# base_1.net
KiCad netlist of a schematic drawn in EAGLE
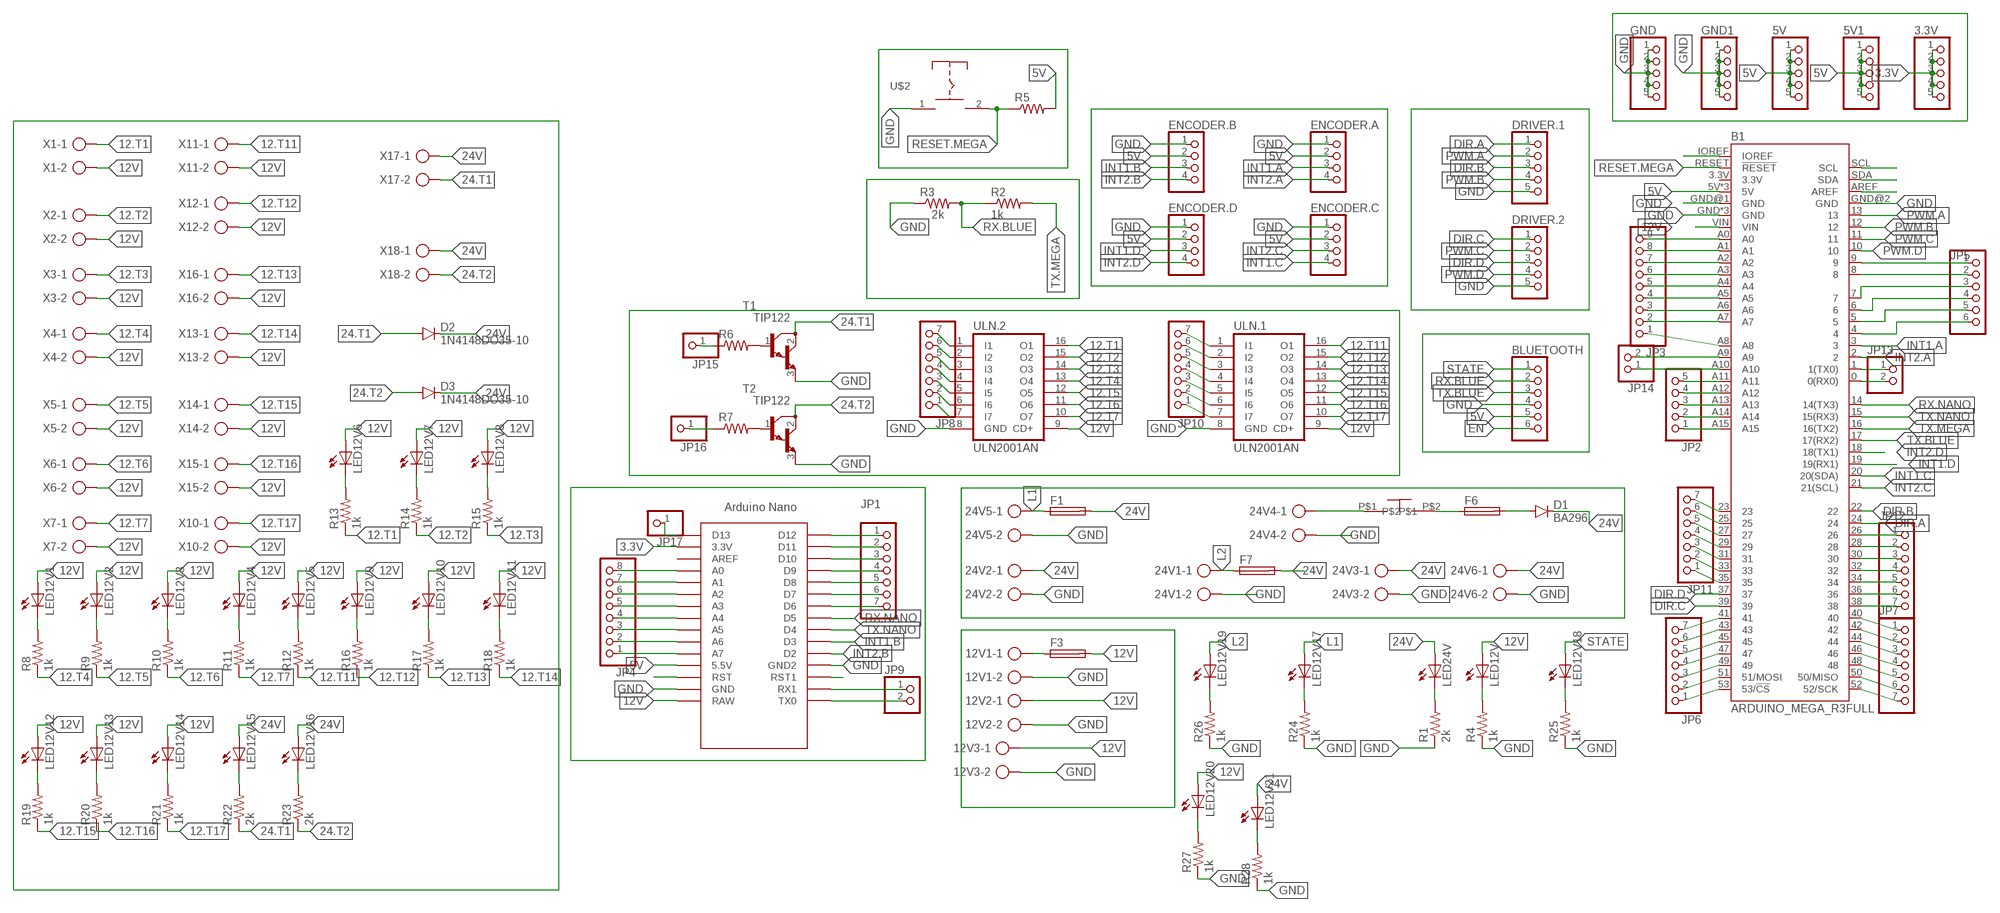
[diagram p0: schematic, sheet 1]

(export (version "E")
  (design (tool "Eeschema 10.0.6"))
  (components
    (comp (ref "3.3V")
      (value "PINHD-1X5")
      (footprint "eagle-import:1X05")
      (libsource (lib "eagle-import") (part "PINHD-1X5"))
    )
    (comp (ref "5V")
      (value "PINHD-1X5")
      (footprint "eagle-import:1X05")
      (libsource (lib "eagle-import") (part "PINHD-1X5"))
    )
    (comp (ref "5V1")
      (value "PINHD-1X5")
      (footprint "eagle-import:1X05")
      (libsource (lib "eagle-import") (part "PINHD-1X5"))
    )
    (comp (ref "12V1")
      (value "AK300/2")
      (footprint "eagle-import:AK300_2")
      (libsource (lib "eagle-import") (part "AK300/2"))
    )
    (comp (ref "12V2")
      (value "AK300/2")
      (footprint "eagle-import:AK300_2")
      (libsource (lib "eagle-import") (part "AK300/2"))
    )
    (comp (ref "12V3")
      (value "AK300/2")
      (footprint "eagle-import:AK300_2")
      (libsource (lib "eagle-import") (part "AK300/2"))
    )
    (comp (ref "24V1")
      (value "W237-113")
      (footprint "eagle-import:W237-113")
      (libsource (lib "eagle-import") (part "W237-113"))
    )
    (comp (ref "24V2")
      (value "AK300/2")
      (footprint "eagle-import:AK300_2")
      (libsource (lib "eagle-import") (part "AK300/2"))
    )
    (comp (ref "24V3")
      (value "AK300/2")
      (footprint "eagle-import:AK300_2")
      (libsource (lib "eagle-import") (part "AK300/2"))
    )
    (comp (ref "24V4")
      (value "W237-113")
      (footprint "eagle-import:W237-113")
      (libsource (lib "eagle-import") (part "W237-113"))
    )
    (comp (ref "24V5")
      (value "W237-113")
      (footprint "eagle-import:W237-113")
      (libsource (lib "eagle-import") (part "W237-113"))
    )
    (comp (ref "24V6")
      (value "AK300/2")
      (footprint "eagle-import:AK300_2")
      (libsource (lib "eagle-import") (part "AK300/2"))
    )
    (comp (ref "B1")
      (value "ARDUINO_MEGA_R3FULL")
      (footprint "eagle-import:ARDUINO_MEGA_NO_SILK")
      (libsource (lib "eagle-import") (part "ARDUINO_MEGA_R3FULL"))
    )
    (comp (ref "BLUETOOTH")
      (value "PINHD-1X6")
      (footprint "eagle-import:1X06")
      (libsource (lib "eagle-import") (part "PINHD-1X6"))
    )
    (comp (ref "D1")
      (value "BA296")
      (footprint "eagle-import:P2-15")
      (libsource (lib "eagle-import") (part "BA296"))
    )
    (comp (ref "D2")
      (value "1N4148DO35-10")
      (footprint "eagle-import:DO35-10")
      (libsource (lib "eagle-import") (part "1N4148DO35-10"))
    )
    (comp (ref "D3")
      (value "1N4148DO35-10")
      (footprint "eagle-import:DO35-10")
      (libsource (lib "eagle-import") (part "1N4148DO35-10"))
    )
    (comp (ref "DRIVER.1")
      (value "PINHD-1X5")
      (footprint "eagle-import:1X05")
      (libsource (lib "eagle-import") (part "PINHD-1X5"))
    )
    (comp (ref "DRIVER.2")
      (value "PINHD-1X5")
      (footprint "eagle-import:1X05")
      (libsource (lib "eagle-import") (part "PINHD-1X5"))
    )
    (comp (ref "ENCODER.A")
      (value "PINHD-1X4")
      (footprint "eagle-import:1X04")
      (libsource (lib "eagle-import") (part "PINHD-1X4"))
    )
    (comp (ref "ENCODER.B")
      (value "PINHD-1X4")
      (footprint "eagle-import:1X04")
      (libsource (lib "eagle-import") (part "PINHD-1X4"))
    )
    (comp (ref "ENCODER.C")
      (value "PINHD-1X4")
      (footprint "eagle-import:1X04")
      (libsource (lib "eagle-import") (part "PINHD-1X4"))
    )
    (comp (ref "ENCODER.D")
      (value "PINHD-1X4")
      (footprint "eagle-import:1X04")
      (libsource (lib "eagle-import") (part "PINHD-1X4"))
    )
    (comp (ref "F1")
      (value "SH22,5A")
      (footprint "eagle-import:SH22,5A")
      (fields (field (name "MPN") "0031.7701.11"))
      (libsource (lib "eagle-import") (part "SH22,5A"))
    )
    (comp (ref "F3")
      (value "SH22,5A")
      (footprint "eagle-import:SH22,5A")
      (fields (field (name "MPN") "0031.7701.11"))
      (libsource (lib "eagle-import") (part "SH22,5A"))
    )
    (comp (ref "F6")
      (value "SH22,5A")
      (footprint "eagle-import:SH22,5A")
      (fields (field (name "MPN") "0031.7701.11"))
      (libsource (lib "eagle-import") (part "SH22,5A"))
    )
    (comp (ref "F7")
      (value "SH22,5A")
      (footprint "eagle-import:SH22,5A")
      (fields (field (name "MPN") "0031.7701.11"))
      (libsource (lib "eagle-import") (part "SH22,5A"))
    )
    (comp (ref "GND")
      (value "PINHD-1X5")
      (footprint "eagle-import:1X05")
      (libsource (lib "eagle-import") (part "PINHD-1X5"))
    )
    (comp (ref "GND1")
      (value "PINHD-1X5")
      (footprint "eagle-import:1X05")
      (libsource (lib "eagle-import") (part "PINHD-1X5"))
    )
    (comp (ref "JP1")
      (value "PINHD-1X7")
      (footprint "eagle-import:1X07")
      (libsource (lib "eagle-import") (part "PINHD-1X7"))
    )
    (comp (ref "JP2")
      (value "PINHD-1X5")
      (footprint "eagle-import:1X05")
      (libsource (lib "eagle-import") (part "PINHD-1X5"))
    )
    (comp (ref "JP3")
      (value "PINHD-1X9")
      (footprint "eagle-import:1X09")
      (libsource (lib "eagle-import") (part "PINHD-1X9"))
    )
    (comp (ref "JP4")
      (value "PINHD-1X8")
      (footprint "eagle-import:1X08")
      (libsource (lib "eagle-import") (part "PINHD-1X8"))
    )
    (comp (ref "JP5")
      (value "PINHD-1X6")
      (footprint "eagle-import:1X06")
      (libsource (lib "eagle-import") (part "PINHD-1X6"))
    )
    (comp (ref "JP6")
      (value "PINHD-1X7")
      (footprint "eagle-import:1X07")
      (libsource (lib "eagle-import") (part "PINHD-1X7"))
    )
    (comp (ref "JP7")
      (value "PINHD-1X7")
      (footprint "eagle-import:1X07")
      (libsource (lib "eagle-import") (part "PINHD-1X7"))
    )
    (comp (ref "JP8")
      (value "PINHD-1X7")
      (footprint "eagle-import:1X07")
      (libsource (lib "eagle-import") (part "PINHD-1X7"))
    )
    (comp (ref "JP9")
      (value "PINHD-1X2")
      (footprint "eagle-import:1X02")
      (libsource (lib "eagle-import") (part "PINHD-1X2"))
    )
    (comp (ref "JP10")
      (value "PINHD-1X7")
      (footprint "eagle-import:1X07")
      (libsource (lib "eagle-import") (part "PINHD-1X7"))
    )
    (comp (ref "JP11")
      (value "PINHD-1X7")
      (footprint "eagle-import:1X07")
      (libsource (lib "eagle-import") (part "PINHD-1X7"))
    )
    (comp (ref "JP12")
      (value "PINHD-1X7")
      (footprint "eagle-import:1X07")
      (libsource (lib "eagle-import") (part "PINHD-1X7"))
    )
    (comp (ref "JP13")
      (value "PINHD-1X2")
      (footprint "eagle-import:1X02")
      (libsource (lib "eagle-import") (part "PINHD-1X2"))
    )
    (comp (ref "JP14")
      (value "PINHD-1X2")
      (footprint "eagle-import:1X02")
      (libsource (lib "eagle-import") (part "PINHD-1X2"))
    )
    (comp (ref "JP15")
      (value "PINHD-1X1")
      (footprint "eagle-import:1X01")
      (libsource (lib "eagle-import") (part "PINHD-1X1"))
    )
    (comp (ref "JP16")
      (value "PINHD-1X1")
      (footprint "eagle-import:1X01")
      (libsource (lib "eagle-import") (part "PINHD-1X1"))
    )
    (comp (ref "JP17")
      (value "PINHD-1X1")
      (footprint "eagle-import:1X01")
      (libsource (lib "eagle-import") (part "PINHD-1X1"))
    )
    (comp (ref "LED12V")
      (value "LED5MM")
      (footprint "eagle-import:LED5MM")
      (libsource (lib "eagle-import") (part "LED5MM"))
    )
    (comp (ref "LED12V1")
      (value "LED3MM")
      (footprint "eagle-import:LED3MM")
      (libsource (lib "eagle-import") (part "LED3MM"))
    )
    (comp (ref "LED12V2")
      (value "LED3MM")
      (footprint "eagle-import:LED3MM")
      (libsource (lib "eagle-import") (part "LED3MM"))
    )
    (comp (ref "LED12V3")
      (value "LED3MM")
      (footprint "eagle-import:LED3MM")
      (libsource (lib "eagle-import") (part "LED3MM"))
    )
    (comp (ref "LED12V4")
      (value "LED3MM")
      (footprint "eagle-import:LED3MM")
      (libsource (lib "eagle-import") (part "LED3MM"))
    )
    (comp (ref "LED12V5")
      (value "LED3MM")
      (footprint "eagle-import:LED3MM")
      (libsource (lib "eagle-import") (part "LED3MM"))
    )
    (comp (ref "LED12V6")
      (value "LED3MM")
      (footprint "eagle-import:LED3MM")
      (libsource (lib "eagle-import") (part "LED3MM"))
    )
    (comp (ref "LED12V7")
      (value "LED3MM")
      (footprint "eagle-import:LED3MM")
      (libsource (lib "eagle-import") (part "LED3MM"))
    )
    (comp (ref "LED12V8")
      (value "LED3MM")
      (footprint "eagle-import:LED3MM")
      (libsource (lib "eagle-import") (part "LED3MM"))
    )
    (comp (ref "LED12V9")
      (value "LED3MM")
      (footprint "eagle-import:LED3MM")
      (libsource (lib "eagle-import") (part "LED3MM"))
    )
    (comp (ref "LED12V10")
      (value "LED3MM")
      (footprint "eagle-import:LED3MM")
      (libsource (lib "eagle-import") (part "LED3MM"))
    )
    (comp (ref "LED12V11")
      (value "LED3MM")
      (footprint "eagle-import:LED3MM")
      (libsource (lib "eagle-import") (part "LED3MM"))
    )
    (comp (ref "LED12V12")
      (value "LED3MM")
      (footprint "eagle-import:LED3MM")
      (libsource (lib "eagle-import") (part "LED3MM"))
    )
    (comp (ref "LED12V13")
      (value "LED3MM")
      (footprint "eagle-import:LED3MM")
      (libsource (lib "eagle-import") (part "LED3MM"))
    )
    (comp (ref "LED12V14")
      (value "LED3MM")
      (footprint "eagle-import:LED3MM")
      (libsource (lib "eagle-import") (part "LED3MM"))
    )
    (comp (ref "LED12V15")
      (value "LED3MM")
      (footprint "eagle-import:LED3MM")
      (libsource (lib "eagle-import") (part "LED3MM"))
    )
    (comp (ref "LED12V16")
      (value "LED3MM")
      (footprint "eagle-import:LED3MM")
      (libsource (lib "eagle-import") (part "LED3MM"))
    )
    (comp (ref "LED12V17")
      (value "LED3MM")
      (footprint "eagle-import:LED3MM")
      (libsource (lib "eagle-import") (part "LED3MM"))
    )
    (comp (ref "LED12V18")
      (value "LED3MM")
      (footprint "eagle-import:LED3MM")
      (libsource (lib "eagle-import") (part "LED3MM"))
    )
    (comp (ref "LED12V19")
      (value "LED3MM")
      (footprint "eagle-import:LED3MM")
      (libsource (lib "eagle-import") (part "LED3MM"))
    )
    (comp (ref "LED12V20")
      (value "LED3MM")
      (footprint "eagle-import:LED3MM")
      (libsource (lib "eagle-import") (part "LED3MM"))
    )
    (comp (ref "LED12V21")
      (value "LED3MM")
      (footprint "eagle-import:LED3MM")
      (libsource (lib "eagle-import") (part "LED3MM"))
    )
    (comp (ref "LED24V")
      (value "LED5MM")
      (footprint "eagle-import:LED5MM")
      (libsource (lib "eagle-import") (part "LED5MM"))
    )
    (comp (ref "R1")
      (value "2k")
      (footprint "eagle-import:0207_10")
      (libsource (lib "eagle-import") (part "R-US_0207/10"))
    )
    (comp (ref "R2")
      (value "1k")
      (footprint "eagle-import:0204_7")
      (libsource (lib "eagle-import") (part "R-US_0204/7"))
    )
    (comp (ref "R3")
      (value "2k")
      (footprint "eagle-import:0207_10")
      (libsource (lib "eagle-import") (part "R-US_0207/10"))
    )
    (comp (ref "R4")
      (value "1k")
      (footprint "eagle-import:0207_10")
      (libsource (lib "eagle-import") (part "R-US_0207/10"))
    )
    (comp (ref "R5")
      (value "R-US_0204/7")
      (footprint "eagle-import:0204_7")
      (libsource (lib "eagle-import") (part "R-US_0204/7"))
    )
    (comp (ref "R6")
      (value "R-US_0207/10")
      (footprint "eagle-import:0207_10")
      (libsource (lib "eagle-import") (part "R-US_0207/10"))
    )
    (comp (ref "R7")
      (value "R-US_0207/10")
      (footprint "eagle-import:0207_10")
      (libsource (lib "eagle-import") (part "R-US_0207/10"))
    )
    (comp (ref "R8")
      (value "1k")
      (footprint "eagle-import:0207_10")
      (libsource (lib "eagle-import") (part "R-US_0207/10"))
    )
    (comp (ref "R9")
      (value "1k")
      (footprint "eagle-import:0207_10")
      (libsource (lib "eagle-import") (part "R-US_0207/10"))
    )
    (comp (ref "R10")
      (value "1k")
      (footprint "eagle-import:0207_10")
      (libsource (lib "eagle-import") (part "R-US_0207/10"))
    )
    (comp (ref "R11")
      (value "1k")
      (footprint "eagle-import:0207_10")
      (libsource (lib "eagle-import") (part "R-US_0207/10"))
    )
    (comp (ref "R12")
      (value "1k")
      (footprint "eagle-import:0207_10")
      (libsource (lib "eagle-import") (part "R-US_0207/10"))
    )
    (comp (ref "R13")
      (value "1k")
      (footprint "eagle-import:0207_10")
      (libsource (lib "eagle-import") (part "R-US_0207/10"))
    )
    (comp (ref "R14")
      (value "1k")
      (footprint "eagle-import:0207_10")
      (libsource (lib "eagle-import") (part "R-US_0207/10"))
    )
    (comp (ref "R15")
      (value "1k")
      (footprint "eagle-import:0207_10")
      (libsource (lib "eagle-import") (part "R-US_0207/10"))
    )
    (comp (ref "R16")
      (value "1k")
      (footprint "eagle-import:0207_10")
      (libsource (lib "eagle-import") (part "R-US_0207/10"))
    )
    (comp (ref "R17")
      (value "1k")
      (footprint "eagle-import:0207_10")
      (libsource (lib "eagle-import") (part "R-US_0207/10"))
    )
    (comp (ref "R18")
      (value "1k")
      (footprint "eagle-import:0207_10")
      (libsource (lib "eagle-import") (part "R-US_0207/10"))
    )
    (comp (ref "R19")
      (value "1k")
      (footprint "eagle-import:0207_10")
      (libsource (lib "eagle-import") (part "R-US_0207/10"))
    )
    (comp (ref "R20")
      (value "1k")
      (footprint "eagle-import:0207_10")
      (libsource (lib "eagle-import") (part "R-US_0207/10"))
    )
    (comp (ref "R21")
      (value "1k")
      (footprint "eagle-import:0207_10")
      (libsource (lib "eagle-import") (part "R-US_0207/10"))
    )
    (comp (ref "R22")
      (value "2k")
      (footprint "eagle-import:0207_10")
      (libsource (lib "eagle-import") (part "R-US_0207/10"))
    )
    (comp (ref "R23")
      (value "2k")
      (footprint "eagle-import:0207_10")
      (libsource (lib "eagle-import") (part "R-US_0207/10"))
    )
    (comp (ref "R24")
      (value "1k")
      (footprint "eagle-import:0207_12")
      (libsource (lib "eagle-import") (part "R-US_0207/12"))
    )
    (comp (ref "R25")
      (value "1k")
      (footprint "eagle-import:0204_5")
      (libsource (lib "eagle-import") (part "R-US_0204/5"))
    )
    (comp (ref "R26")
      (value "1k")
      (footprint "eagle-import:0204_5")
      (libsource (lib "eagle-import") (part "R-US_0204/5"))
    )
    (comp (ref "R27")
      (value "1k")
      (footprint "eagle-import:0204_5")
      (libsource (lib "eagle-import") (part "R-US_0204/5"))
    )
    (comp (ref "R28")
      (value "1k")
      (footprint "eagle-import:0204_5")
      (libsource (lib "eagle-import") (part "R-US_0204/5"))
    )
    (comp (ref "T1")
      (value "TIP122")
      (footprint "eagle-import:TO220")
      (libsource (lib "eagle-import") (part "TIP122"))
    )
    (comp (ref "T2")
      (value "TIP122")
      (footprint "eagle-import:TO220")
      (libsource (lib "eagle-import") (part "TIP122"))
    )
    (comp (ref "U$1")
      (value "NANO")
      (footprint "eagle-import:NANO")
      (libsource (lib "eagle-import") (part "NANO"))
    )
    (comp (ref "U$2")
      (value "PUSHBOTTON")
      (footprint "eagle-import:PUSHBOTTON")
      (libsource (lib "eagle-import") (part "PUSHBOTTON"))
    )
    (comp (ref "U$3")
      (value "ON_OFF")
      (footprint "eagle-import:ON_OFF")
      (libsource (lib "eagle-import") (part "ON_OFF"))
    )
    (comp (ref "ULN.1")
      (value "ULN2001AN")
      (footprint "eagle-import:DIL16")
      (libsource (lib "eagle-import") (part "ULN2001AN"))
    )
    (comp (ref "ULN.2")
      (value "ULN2001AN")
      (footprint "eagle-import:DIL16")
      (libsource (lib "eagle-import") (part "ULN2001AN"))
    )
    (comp (ref "X1")
      (value "AK300/2")
      (footprint "eagle-import:AK300_2")
      (libsource (lib "eagle-import") (part "AK300/2"))
    )
    (comp (ref "X2")
      (value "AK300/2")
      (footprint "eagle-import:AK300_2")
      (libsource (lib "eagle-import") (part "AK300/2"))
    )
    (comp (ref "X3")
      (value "AK300/2")
      (footprint "eagle-import:AK300_2")
      (libsource (lib "eagle-import") (part "AK300/2"))
    )
    (comp (ref "X4")
      (value "AK300/2")
      (footprint "eagle-import:AK300_2")
      (libsource (lib "eagle-import") (part "AK300/2"))
    )
    (comp (ref "X5")
      (value "AK300/2")
      (footprint "eagle-import:AK300_2")
      (libsource (lib "eagle-import") (part "AK300/2"))
    )
    (comp (ref "X6")
      (value "AK300/2")
      (footprint "eagle-import:AK300_2")
      (libsource (lib "eagle-import") (part "AK300/2"))
    )
    (comp (ref "X7")
      (value "AK300/2")
      (footprint "eagle-import:AK300_2")
      (libsource (lib "eagle-import") (part "AK300/2"))
    )
    (comp (ref "X10")
      (value "AK300/2")
      (footprint "eagle-import:AK300_2")
      (libsource (lib "eagle-import") (part "AK300/2"))
    )
    (comp (ref "X11")
      (value "AK300/2")
      (footprint "eagle-import:AK300_2")
      (libsource (lib "eagle-import") (part "AK300/2"))
    )
    (comp (ref "X12")
      (value "AK300/2")
      (footprint "eagle-import:AK300_2")
      (libsource (lib "eagle-import") (part "AK300/2"))
    )
    (comp (ref "X13")
      (value "AK300/2")
      (footprint "eagle-import:AK300_2")
      (libsource (lib "eagle-import") (part "AK300/2"))
    )
    (comp (ref "X14")
      (value "AK300/2")
      (footprint "eagle-import:AK300_2")
      (libsource (lib "eagle-import") (part "AK300/2"))
    )
    (comp (ref "X15")
      (value "AK300/2")
      (footprint "eagle-import:AK300_2")
      (libsource (lib "eagle-import") (part "AK300/2"))
    )
    (comp (ref "X16")
      (value "AK300/2")
      (footprint "eagle-import:AK300_2")
      (libsource (lib "eagle-import") (part "AK300/2"))
    )
    (comp (ref "X17")
      (value "AK300/2")
      (footprint "eagle-import:AK300_2")
      (libsource (lib "eagle-import") (part "AK300/2"))
    )
    (comp (ref "X18")
      (value "AK300/2")
      (footprint "eagle-import:AK300_2")
      (libsource (lib "eagle-import") (part "AK300/2"))
    )
  )
  (nets
    (net (code "1") (name "3.3V") (class "Default")
      (node (ref "3.3V") (pin "1") (pinfunction "1_1") (pintype "passive"))
      (node (ref "3.3V") (pin "2") (pinfunction "2_2") (pintype "passive"))
      (node (ref "3.3V") (pin "3") (pinfunction "3_3") (pintype "passive"))
      (node (ref "3.3V") (pin "4") (pinfunction "4_4") (pintype "passive"))
      (node (ref "3.3V") (pin "5") (pinfunction "5_5") (pintype "passive"))
      (node (ref "U$1") (pin "3.3V") (pinfunction "3.3V_3.3V") (pintype "bidirectional"))
    )
    (net (code "2") (name "5V") (class "Default")
      (node (ref "5V") (pin "1") (pinfunction "1_1") (pintype "passive"))
      (node (ref "5V") (pin "2") (pinfunction "2_2") (pintype "passive"))
      (node (ref "5V") (pin "3") (pinfunction "3_3") (pintype "passive"))
      (node (ref "5V") (pin "4") (pinfunction "4_4") (pintype "passive"))
      (node (ref "5V") (pin "5") (pinfunction "5_5") (pintype "passive"))
      (node (ref "5V1") (pin "1") (pinfunction "1_1") (pintype "passive"))
      (node (ref "5V1") (pin "2") (pinfunction "2_2") (pintype "passive"))
      (node (ref "5V1") (pin "3") (pinfunction "3_3") (pintype "passive"))
      (node (ref "5V1") (pin "4") (pinfunction "4_4") (pintype "passive"))
      (node (ref "5V1") (pin "5") (pinfunction "5_5") (pintype "passive"))
      (node (ref "B1") (pin "5V") (pinfunction "5V_5V") (pintype "bidirectional"))
      (node (ref "B1") (pin "5V@1") (pinfunction "5V_5V@1") (pintype "bidirectional"))
      (node (ref "B1") (pin "5V@2") (pinfunction "5V_5V@2") (pintype "bidirectional"))
      (node (ref "BLUETOOTH") (pin "5") (pinfunction "5_5") (pintype "passive"))
      (node (ref "ENCODER.A") (pin "2") (pinfunction "2_2") (pintype "passive"))
      (node (ref "ENCODER.B") (pin "2") (pinfunction "2_2") (pintype "passive"))
      (node (ref "ENCODER.C") (pin "2") (pinfunction "2_2") (pintype "passive"))
      (node (ref "ENCODER.D") (pin "2") (pinfunction "2_2") (pintype "passive"))
      (node (ref "R5") (pin "2") (pinfunction "2_2") (pintype "passive"))
      (node (ref "U$1") (pin "5V") (pinfunction "5.5V_5V") (pintype "bidirectional"))
    )
    (net (code "3") (name "12.T1") (class "Default")
      (node (ref "R13") (pin "1") (pinfunction "1_1") (pintype "passive"))
      (node (ref "ULN.2") (pin "16") (pinfunction "O1_16") (pintype "open_collector"))
      (node (ref "X1") (pin "1") (pinfunction "KL_1") (pintype "passive"))
    )
    (net (code "4") (name "12.T2") (class "Default")
      (node (ref "R14") (pin "1") (pinfunction "1_1") (pintype "passive"))
      (node (ref "ULN.2") (pin "15") (pinfunction "O2_15") (pintype "open_collector"))
      (node (ref "X2") (pin "1") (pinfunction "KL_1") (pintype "passive"))
    )
    (net (code "5") (name "12.T3") (class "Default")
      (node (ref "R15") (pin "1") (pinfunction "1_1") (pintype "passive"))
      (node (ref "ULN.2") (pin "14") (pinfunction "O3_14") (pintype "open_collector"))
      (node (ref "X3") (pin "1") (pinfunction "KL_1") (pintype "passive"))
    )
    (net (code "6") (name "12.T4") (class "Default")
      (node (ref "R8") (pin "1") (pinfunction "1_1") (pintype "passive"))
      (node (ref "ULN.2") (pin "13") (pinfunction "O4_13") (pintype "open_collector"))
      (node (ref "X4") (pin "1") (pinfunction "KL_1") (pintype "passive"))
    )
    (net (code "7") (name "12.T5") (class "Default")
      (node (ref "R9") (pin "1") (pinfunction "1_1") (pintype "passive"))
      (node (ref "ULN.2") (pin "12") (pinfunction "O5_12") (pintype "open_collector"))
      (node (ref "X5") (pin "1") (pinfunction "KL_1") (pintype "passive"))
    )
    (net (code "8") (name "12.T6") (class "Default")
      (node (ref "R10") (pin "1") (pinfunction "1_1") (pintype "passive"))
      (node (ref "ULN.2") (pin "11") (pinfunction "O6_11") (pintype "open_collector"))
      (node (ref "X6") (pin "1") (pinfunction "KL_1") (pintype "passive"))
    )
    (net (code "9") (name "12.T7") (class "Default")
      (node (ref "R11") (pin "1") (pinfunction "1_1") (pintype "passive"))
      (node (ref "ULN.2") (pin "10") (pinfunction "O7_10") (pintype "open_collector"))
      (node (ref "X7") (pin "1") (pinfunction "KL_1") (pintype "passive"))
    )
    (net (code "10") (name "12.T11") (class "Default")
      (node (ref "R12") (pin "1") (pinfunction "1_1") (pintype "passive"))
      (node (ref "ULN.1") (pin "16") (pinfunction "O1_16") (pintype "open_collector"))
      (node (ref "X11") (pin "1") (pinfunction "KL_1") (pintype "passive"))
    )
    (net (code "11") (name "12.T12") (class "Default")
      (node (ref "R16") (pin "1") (pinfunction "1_1") (pintype "passive"))
      (node (ref "ULN.1") (pin "15") (pinfunction "O2_15") (pintype "open_collector"))
      (node (ref "X12") (pin "1") (pinfunction "KL_1") (pintype "passive"))
    )
    (net (code "12") (name "12.T13") (class "Default")
      (node (ref "R17") (pin "1") (pinfunction "1_1") (pintype "passive"))
      (node (ref "ULN.1") (pin "14") (pinfunction "O3_14") (pintype "open_collector"))
      (node (ref "X16") (pin "1") (pinfunction "KL_1") (pintype "passive"))
    )
    (net (code "13") (name "12.T14") (class "Default")
      (node (ref "R18") (pin "1") (pinfunction "1_1") (pintype "passive"))
      (node (ref "ULN.1") (pin "13") (pinfunction "O4_13") (pintype "open_collector"))
      (node (ref "X13") (pin "1") (pinfunction "KL_1") (pintype "passive"))
    )
    (net (code "14") (name "12.T15") (class "Default")
      (node (ref "R19") (pin "1") (pinfunction "1_1") (pintype "passive"))
      (node (ref "ULN.1") (pin "12") (pinfunction "O5_12") (pintype "open_collector"))
      (node (ref "X14") (pin "1") (pinfunction "KL_1") (pintype "passive"))
    )
    (net (code "15") (name "12.T16") (class "Default")
      (node (ref "R20") (pin "1") (pinfunction "1_1") (pintype "passive"))
      (node (ref "ULN.1") (pin "11") (pinfunction "O6_11") (pintype "open_collector"))
      (node (ref "X15") (pin "1") (pinfunction "KL_1") (pintype "passive"))
    )
    (net (code "16") (name "12.T17") (class "Default")
      (node (ref "R21") (pin "1") (pinfunction "1_1") (pintype "passive"))
      (node (ref "ULN.1") (pin "10") (pinfunction "O7_10") (pintype "open_collector"))
      (node (ref "X10") (pin "1") (pinfunction "KL_1") (pintype "passive"))
    )
    (net (code "17") (name "12V") (class "Default")
      (node (ref "12V2") (pin "1") (pinfunction "KL_1") (pintype "passive"))
      (node (ref "12V3") (pin "1") (pinfunction "KL_1") (pintype "passive"))
      (node (ref "B1") (pin "VIN") (pinfunction "VIN_VIN") (pintype "bidirectional"))
      (node (ref "F3") (pin "2") (pinfunction "2_2") (pintype "passive"))
      (node (ref "LED12V") (pin "A") (pinfunction "A_A") (pintype "passive"))
      (node (ref "LED12V1") (pin "A") (pinfunction "A_A") (pintype "passive"))
      (node (ref "LED12V10") (pin "A") (pinfunction "A_A") (pintype "passive"))
      (node (ref "LED12V11") (pin "A") (pinfunction "A_A") (pintype "passive"))
      (node (ref "LED12V12") (pin "A") (pinfunction "A_A") (pintype "passive"))
      (node (ref "LED12V13") (pin "A") (pinfunction "A_A") (pintype "passive"))
      (node (ref "LED12V14") (pin "A") (pinfunction "A_A") (pintype "passive"))
      (node (ref "LED12V2") (pin "A") (pinfunction "A_A") (pintype "passive"))
      (node (ref "LED12V20") (pin "A") (pinfunction "A_A") (pintype "passive"))
      (node (ref "LED12V3") (pin "A") (pinfunction "A_A") (pintype "passive"))
      (node (ref "LED12V4") (pin "A") (pinfunction "A_A") (pintype "passive"))
      (node (ref "LED12V5") (pin "A") (pinfunction "A_A") (pintype "passive"))
      (node (ref "LED12V6") (pin "A") (pinfunction "A_A") (pintype "passive"))
      (node (ref "LED12V7") (pin "A") (pinfunction "A_A") (pintype "passive"))
      (node (ref "LED12V8") (pin "A") (pinfunction "A_A") (pintype "passive"))
      (node (ref "LED12V9") (pin "A") (pinfunction "A_A") (pintype "passive"))
      (node (ref "U$1") (pin "RAW") (pinfunction "RAW_RAW") (pintype "bidirectional"))
      (node (ref "ULN.1") (pin "9") (pinfunction "CD+_9") (pintype "passive"))
      (node (ref "ULN.2") (pin "9") (pinfunction "CD+_9") (pintype "passive"))
      (node (ref "X1") (pin "2") (pinfunction "KL_2") (pintype "passive"))
      (node (ref "X10") (pin "2") (pinfunction "KL_2") (pintype "passive"))
      (node (ref "X11") (pin "2") (pinfunction "KL_2") (pintype "passive"))
      (node (ref "X12") (pin "2") (pinfunction "KL_2") (pintype "passive"))
      (node (ref "X13") (pin "2") (pinfunction "KL_2") (pintype "passive"))
      (node (ref "X14") (pin "2") (pinfunction "KL_2") (pintype "passive"))
      (node (ref "X15") (pin "2") (pinfunction "KL_2") (pintype "passive"))
      (node (ref "X16") (pin "2") (pinfunction "KL_2") (pintype "passive"))
      (node (ref "X2") (pin "2") (pinfunction "KL_2") (pintype "passive"))
      (node (ref "X3") (pin "2") (pinfunction "KL_2") (pintype "passive"))
      (node (ref "X4") (pin "2") (pinfunction "KL_2") (pintype "passive"))
      (node (ref "X5") (pin "2") (pinfunction "KL_2") (pintype "passive"))
      (node (ref "X6") (pin "2") (pinfunction "KL_2") (pintype "passive"))
      (node (ref "X7") (pin "2") (pinfunction "KL_2") (pintype "passive"))
    )
    (net (code "18") (name "24.T1") (class "Default")
      (node (ref "D2") (pin "A") (pinfunction "A_A") (pintype "passive"))
      (node (ref "R22") (pin "1") (pinfunction "1_1") (pintype "passive"))
      (node (ref "T1") (pin "2") (pinfunction "C_2") (pintype "passive"))
      (node (ref "X17") (pin "2") (pinfunction "KL_2") (pintype "passive"))
    )
    (net (code "19") (name "24.T2") (class "Default")
      (node (ref "D3") (pin "A") (pinfunction "A_A") (pintype "passive"))
      (node (ref "R23") (pin "1") (pinfunction "1_1") (pintype "passive"))
      (node (ref "T2") (pin "2") (pinfunction "C_2") (pintype "passive"))
      (node (ref "X18") (pin "2") (pinfunction "KL_2") (pintype "passive"))
    )
    (net (code "20") (name "24V") (class "Default")
      (node (ref "24V2") (pin "1") (pinfunction "KL_1") (pintype "passive"))
      (node (ref "24V3") (pin "1") (pinfunction "KL_1") (pintype "passive"))
      (node (ref "24V6") (pin "1") (pinfunction "KL_1") (pintype "passive"))
      (node (ref "D1") (pin "C") (pinfunction "C_C") (pintype "passive"))
      (node (ref "D2") (pin "C") (pinfunction "C_C") (pintype "passive"))
      (node (ref "D3") (pin "C") (pinfunction "C_C") (pintype "passive"))
      (node (ref "F1") (pin "2") (pinfunction "2_2") (pintype "passive"))
      (node (ref "F7") (pin "2") (pinfunction "2_2") (pintype "passive"))
      (node (ref "LED12V15") (pin "A") (pinfunction "A_A") (pintype "passive"))
      (node (ref "LED12V16") (pin "A") (pinfunction "A_A") (pintype "passive"))
      (node (ref "LED12V21") (pin "A") (pinfunction "A_A") (pintype "passive"))
      (node (ref "LED24V") (pin "A") (pinfunction "A_A") (pintype "passive"))
      (node (ref "X17") (pin "1") (pinfunction "KL_1") (pintype "passive"))
      (node (ref "X18") (pin "1") (pinfunction "KL_1") (pintype "passive"))
    )
    (net (code "21") (name "DIR.A") (class "Default")
      (node (ref "B1") (pin "24") (pinfunction "24_24") (pintype "bidirectional"))
      (node (ref "DRIVER.1") (pin "1") (pinfunction "1_1") (pintype "passive"))
    )
    (net (code "22") (name "DIR.B") (class "Default")
      (node (ref "B1") (pin "22") (pinfunction "22_22") (pintype "bidirectional"))
      (node (ref "DRIVER.1") (pin "3") (pinfunction "3_3") (pintype "passive"))
    )
    (net (code "23") (name "DIR.C") (class "Default")
      (node (ref "B1") (pin "39") (pinfunction "39_39") (pintype "bidirectional"))
      (node (ref "DRIVER.2") (pin "1") (pinfunction "1_1") (pintype "passive"))
    )
    (net (code "24") (name "DIR.D") (class "Default")
      (node (ref "B1") (pin "37") (pinfunction "37_37") (pintype "bidirectional"))
      (node (ref "DRIVER.2") (pin "3") (pinfunction "3_3") (pintype "passive"))
    )
    (net (code "25") (name "EN") (class "Default")
      (node (ref "BLUETOOTH") (pin "6") (pinfunction "6_6") (pintype "passive"))
    )
    (net (code "26") (name "GND") (class "Default")
      (node (ref "12V1") (pin "2") (pinfunction "KL_2") (pintype "passive"))
      (node (ref "12V2") (pin "2") (pinfunction "KL_2") (pintype "passive"))
      (node (ref "12V3") (pin "2") (pinfunction "KL_2") (pintype "passive"))
      (node (ref "24V1") (pin "2") (pinfunction "KL_2") (pintype "passive"))
      (node (ref "24V2") (pin "2") (pinfunction "KL_2") (pintype "passive"))
      (node (ref "24V3") (pin "2") (pinfunction "KL_2") (pintype "passive"))
      (node (ref "24V4") (pin "2") (pinfunction "KL_2") (pintype "passive"))
      (node (ref "24V5") (pin "2") (pinfunction "KL_2") (pintype "passive"))
      (node (ref "24V6") (pin "2") (pinfunction "KL_2") (pintype "passive"))
      (node (ref "B1") (pin "GND") (pinfunction "GND_GND") (pintype "bidirectional"))
      (node (ref "B1") (pin "GND@1") (pinfunction "GND_GND@1") (pintype "bidirectional"))
      (node (ref "B1") (pin "GND@2") (pinfunction "GND_GND@2") (pintype "bidirectional"))
      (node (ref "B1") (pin "GND@3") (pinfunction "GND_GND@3") (pintype "bidirectional"))
      (node (ref "B1") (pin "GND@4") (pinfunction "GND_GND@4") (pintype "bidirectional"))
      (node (ref "BLUETOOTH") (pin "4") (pinfunction "4_4") (pintype "passive"))
      (node (ref "DRIVER.1") (pin "5") (pinfunction "5_5") (pintype "passive"))
      (node (ref "DRIVER.2") (pin "5") (pinfunction "5_5") (pintype "passive"))
      (node (ref "ENCODER.A") (pin "1") (pinfunction "1_1") (pintype "passive"))
      (node (ref "ENCODER.B") (pin "1") (pinfunction "1_1") (pintype "passive"))
      (node (ref "ENCODER.C") (pin "1") (pinfunction "1_1") (pintype "passive"))
      (node (ref "ENCODER.D") (pin "1") (pinfunction "1_1") (pintype "passive"))
      (node (ref "GND") (pin "1") (pinfunction "1_1") (pintype "passive"))
      (node (ref "GND") (pin "2") (pinfunction "2_2") (pintype "passive"))
      (node (ref "GND") (pin "3") (pinfunction "3_3") (pintype "passive"))
      (node (ref "GND") (pin "4") (pinfunction "4_4") (pintype "passive"))
      (node (ref "GND") (pin "5") (pinfunction "5_5") (pintype "passive"))
      (node (ref "GND1") (pin "1") (pinfunction "1_1") (pintype "passive"))
      (node (ref "GND1") (pin "2") (pinfunction "2_2") (pintype "passive"))
      (node (ref "GND1") (pin "3") (pinfunction "3_3") (pintype "passive"))
      (node (ref "GND1") (pin "4") (pinfunction "4_4") (pintype "passive"))
      (node (ref "GND1") (pin "5") (pinfunction "5_5") (pintype "passive"))
      (node (ref "R1") (pin "1") (pinfunction "1_1") (pintype "passive"))
      (node (ref "R24") (pin "1") (pinfunction "1_1") (pintype "passive"))
      (node (ref "R25") (pin "1") (pinfunction "1_1") (pintype "passive"))
      (node (ref "R26") (pin "1") (pinfunction "1_1") (pintype "passive"))
      (node (ref "R27") (pin "1") (pinfunction "1_1") (pintype "passive"))
      (node (ref "R28") (pin "1") (pinfunction "1_1") (pintype "passive"))
      (node (ref "R3") (pin "1") (pinfunction "1_1") (pintype "passive"))
      (node (ref "R4") (pin "1") (pinfunction "1_1") (pintype "passive"))
      (node (ref "T1") (pin "3") (pinfunction "E_3") (pintype "passive"))
      (node (ref "T2") (pin "3") (pinfunction "E_3") (pintype "passive"))
      (node (ref "U$1") (pin "GND") (pinfunction "GND_GND") (pintype "bidirectional"))
      (node (ref "U$1") (pin "GND1") (pinfunction "GND2_GND1") (pintype "bidirectional"))
      (node (ref "U$2") (pin "1") (pinfunction "1_1") (pintype "bidirectional"))
      (node (ref "ULN.1") (pin "8") (pinfunction "GND_8") (pintype "power_in"))
      (node (ref "ULN.2") (pin "8") (pinfunction "GND_8") (pintype "power_in"))
    )
    (net (code "27") (name "INT1.A") (class "Default")
      (node (ref "B1") (pin "3") (pinfunction "3_3") (pintype "bidirectional"))
      (node (ref "ENCODER.A") (pin "3") (pinfunction "3_3") (pintype "passive"))
    )
    (net (code "28") (name "INT1.B") (class "Default")
      (node (ref "ENCODER.B") (pin "3") (pinfunction "3_3") (pintype "passive"))
      (node (ref "U$1") (pin "D3") (pinfunction "D3_D3") (pintype "bidirectional"))
    )
    (net (code "29") (name "INT1.C") (class "Default")
      (node (ref "B1") (pin "20") (pinfunction "20(SDA)_20") (pintype "bidirectional"))
      (node (ref "ENCODER.C") (pin "4") (pinfunction "4_4") (pintype "passive"))
    )
    (net (code "30") (name "INT1.D") (class "Default")
      (node (ref "B1") (pin "19") (pinfunction "19(RX1)_19") (pintype "bidirectional"))
      (node (ref "ENCODER.D") (pin "3") (pinfunction "3_3") (pintype "passive"))
    )
    (net (code "31") (name "INT2.A") (class "Default")
      (node (ref "B1") (pin "2") (pinfunction "2_2") (pintype "bidirectional"))
      (node (ref "ENCODER.A") (pin "4") (pinfunction "4_4") (pintype "passive"))
    )
    (net (code "32") (name "INT2.B") (class "Default")
      (node (ref "ENCODER.B") (pin "4") (pinfunction "4_4") (pintype "passive"))
      (node (ref "U$1") (pin "D2") (pinfunction "D2_D2") (pintype "bidirectional"))
    )
    (net (code "33") (name "INT2.C") (class "Default")
      (node (ref "B1") (pin "21") (pinfunction "21(SCL)_21") (pintype "bidirectional"))
      (node (ref "ENCODER.C") (pin "3") (pinfunction "3_3") (pintype "passive"))
    )
    (net (code "34") (name "INT2.D") (class "Default")
      (node (ref "B1") (pin "18") (pinfunction "18(TX1)_18") (pintype "bidirectional"))
      (node (ref "ENCODER.D") (pin "4") (pinfunction "4_4") (pintype "passive"))
    )
    (net (code "35") (name "L1") (class "Default")
      (node (ref "24V5") (pin "1") (pinfunction "KL_1") (pintype "passive"))
      (node (ref "F1") (pin "1") (pinfunction "1_1") (pintype "passive"))
      (node (ref "LED12V17") (pin "A") (pinfunction "A_A") (pintype "passive"))
    )
    (net (code "36") (name "L2") (class "Default")
      (node (ref "24V1") (pin "1") (pinfunction "KL_1") (pintype "passive"))
      (node (ref "F7") (pin "1") (pinfunction "1_1") (pintype "passive"))
      (node (ref "LED12V19") (pin "A") (pinfunction "A_A") (pintype "passive"))
    )
    (net (code "37") (name "Net-(12V1A-KL)") (class "Default")
      (node (ref "12V1") (pin "1") (pinfunction "KL_1") (pintype "passive"))
      (node (ref "F3") (pin "1") (pinfunction "1_1") (pintype "passive"))
    )
    (net (code "38") (name "Net-(24V4A-KL)") (class "Default")
      (node (ref "24V4") (pin "1") (pinfunction "KL_1") (pintype "passive"))
      (node (ref "U$3") (pin "P$1") (pinfunction "P$1_P$1") (pintype "bidirectional"))
    )
    (net (code "39") (name "Net-(B1-0(RX0))") (class "Default")
      (node (ref "B1") (pin "0") (pinfunction "0(RX0)_0") (pintype "bidirectional"))
      (node (ref "JP13") (pin "2") (pinfunction "2_2") (pintype "passive"))
    )
    (net (code "40") (name "Net-(B1-1(TX0))") (class "Default")
      (node (ref "B1") (pin "1") (pinfunction "1(TX0)_1") (pintype "bidirectional"))
      (node (ref "JP13") (pin "1") (pinfunction "1_1") (pintype "passive"))
    )
    (net (code "41") (name "Net-(B1-50{slash}MISO)") (class "Default")
      (node (ref "B1") (pin "50") (pinfunction "50/MISO_50") (pintype "bidirectional"))
      (node (ref "JP7") (pin "6") (pinfunction "6_6") (pintype "passive"))
    )
    (net (code "42") (name "Net-(B1-51{slash}MOSI)") (class "Default")
      (node (ref "B1") (pin "51") (pinfunction "51/MOSI_51") (pintype "bidirectional"))
      (node (ref "JP6") (pin "2") (pinfunction "2_2") (pintype "passive"))
    )
    (net (code "43") (name "Net-(B1-52{slash}SCK)") (class "Default")
      (node (ref "B1") (pin "52") (pinfunction "52/SCK_52") (pintype "bidirectional"))
      (node (ref "JP7") (pin "7") (pinfunction "7_7") (pintype "passive"))
    )
    (net (code "44") (name "Net-(B1-53{slash}~{CS})") (class "Default")
      (node (ref "B1") (pin "53") (pinfunction "53/~{CS}_53") (pintype "bidirectional"))
      (node (ref "JP6") (pin "1") (pinfunction "1_1") (pintype "passive"))
    )
    (net (code "45") (name "Net-(B1-Pad4)") (class "Default")
      (node (ref "B1") (pin "4") (pinfunction "4_4") (pintype "bidirectional"))
      (node (ref "JP5") (pin "6") (pinfunction "6_6") (pintype "passive"))
    )
    (net (code "46") (name "Net-(B1-Pad5)") (class "Default")
      (node (ref "B1") (pin "5") (pinfunction "5_5") (pintype "bidirectional"))
      (node (ref "JP5") (pin "5") (pinfunction "5_5") (pintype "passive"))
    )
    (net (code "47") (name "Net-(B1-Pad6)") (class "Default")
      (node (ref "B1") (pin "6") (pinfunction "6_6") (pintype "bidirectional"))
      (node (ref "JP5") (pin "4") (pinfunction "4_4") (pintype "passive"))
    )
    (net (code "48") (name "Net-(B1-Pad7)") (class "Default")
      (node (ref "B1") (pin "7") (pinfunction "7_7") (pintype "bidirectional"))
      (node (ref "JP5") (pin "3") (pinfunction "3_3") (pintype "passive"))
    )
    (net (code "49") (name "Net-(B1-Pad8)") (class "Default")
      (node (ref "B1") (pin "8") (pinfunction "8_8") (pintype "bidirectional"))
      (node (ref "JP5") (pin "2") (pinfunction "2_2") (pintype "passive"))
    )
    (net (code "50") (name "Net-(B1-Pad9)") (class "Default")
      (node (ref "B1") (pin "9") (pinfunction "9_9") (pintype "bidirectional"))
      (node (ref "JP5") (pin "1") (pinfunction "1_1") (pintype "passive"))
    )
    (net (code "51") (name "Net-(B1-Pad23)") (class "Default")
      (node (ref "B1") (pin "23") (pinfunction "23_23") (pintype "bidirectional"))
      (node (ref "JP11") (pin "7") (pinfunction "7_7") (pintype "passive"))
    )
    (net (code "52") (name "Net-(B1-Pad25)") (class "Default")
      (node (ref "B1") (pin "25") (pinfunction "25_25") (pintype "bidirectional"))
      (node (ref "JP11") (pin "6") (pinfunction "6_6") (pintype "passive"))
    )
    (net (code "53") (name "Net-(B1-Pad26)") (class "Default")
      (node (ref "B1") (pin "26") (pinfunction "26_26") (pintype "bidirectional"))
      (node (ref "JP12") (pin "1") (pinfunction "1_1") (pintype "passive"))
    )
    (net (code "54") (name "Net-(B1-Pad27)") (class "Default")
      (node (ref "B1") (pin "27") (pinfunction "27_27") (pintype "bidirectional"))
      (node (ref "JP11") (pin "5") (pinfunction "5_5") (pintype "passive"))
    )
    (net (code "55") (name "Net-(B1-Pad28)") (class "Default")
      (node (ref "B1") (pin "28") (pinfunction "28_28") (pintype "bidirectional"))
      (node (ref "JP12") (pin "2") (pinfunction "2_2") (pintype "passive"))
    )
    (net (code "56") (name "Net-(B1-Pad29)") (class "Default")
      (node (ref "B1") (pin "29") (pinfunction "29_29") (pintype "bidirectional"))
      (node (ref "JP11") (pin "4") (pinfunction "4_4") (pintype "passive"))
    )
    (net (code "57") (name "Net-(B1-Pad30)") (class "Default")
      (node (ref "B1") (pin "30") (pinfunction "30_30") (pintype "bidirectional"))
      (node (ref "JP12") (pin "3") (pinfunction "3_3") (pintype "passive"))
    )
    (net (code "58") (name "Net-(B1-Pad31)") (class "Default")
      (node (ref "B1") (pin "31") (pinfunction "31_31") (pintype "bidirectional"))
      (node (ref "JP11") (pin "3") (pinfunction "3_3") (pintype "passive"))
    )
    (net (code "59") (name "Net-(B1-Pad32)") (class "Default")
      (node (ref "B1") (pin "32") (pinfunction "32_32") (pintype "bidirectional"))
      (node (ref "JP12") (pin "4") (pinfunction "4_4") (pintype "passive"))
    )
    (net (code "60") (name "Net-(B1-Pad33)") (class "Default")
      (node (ref "B1") (pin "33") (pinfunction "33_33") (pintype "bidirectional"))
      (node (ref "JP11") (pin "2") (pinfunction "2_2") (pintype "passive"))
    )
    (net (code "61") (name "Net-(B1-Pad34)") (class "Default")
      (node (ref "B1") (pin "34") (pinfunction "34_34") (pintype "bidirectional"))
      (node (ref "JP12") (pin "5") (pinfunction "5_5") (pintype "passive"))
    )
    (net (code "62") (name "Net-(B1-Pad35)") (class "Default")
      (node (ref "B1") (pin "35") (pinfunction "35_35") (pintype "bidirectional"))
      (node (ref "JP11") (pin "1") (pinfunction "1_1") (pintype "passive"))
    )
    (net (code "63") (name "Net-(B1-Pad36)") (class "Default")
      (node (ref "B1") (pin "36") (pinfunction "36_36") (pintype "bidirectional"))
      (node (ref "JP12") (pin "6") (pinfunction "6_6") (pintype "passive"))
    )
    (net (code "64") (name "Net-(B1-Pad38)") (class "Default")
      (node (ref "B1") (pin "38") (pinfunction "38_38") (pintype "bidirectional"))
      (node (ref "JP12") (pin "7") (pinfunction "7_7") (pintype "passive"))
    )
    (net (code "65") (name "Net-(B1-Pad40)") (class "Default")
      (node (ref "B1") (pin "40") (pinfunction "40_40") (pintype "bidirectional"))
      (node (ref "JP7") (pin "1") (pinfunction "1_1") (pintype "passive"))
    )
    (net (code "66") (name "Net-(B1-Pad41)") (class "Default")
      (node (ref "B1") (pin "41") (pinfunction "41_41") (pintype "bidirectional"))
      (node (ref "JP6") (pin "7") (pinfunction "7_7") (pintype "passive"))
    )
    (net (code "67") (name "Net-(B1-Pad42)") (class "Default")
      (node (ref "B1") (pin "42") (pinfunction "42_42") (pintype "bidirectional"))
      (node (ref "JP7") (pin "2") (pinfunction "2_2") (pintype "passive"))
    )
    (net (code "68") (name "Net-(B1-Pad43)") (class "Default")
      (node (ref "B1") (pin "43") (pinfunction "43_43") (pintype "bidirectional"))
      (node (ref "JP6") (pin "6") (pinfunction "6_6") (pintype "passive"))
    )
    (net (code "69") (name "Net-(B1-Pad44)") (class "Default")
      (node (ref "B1") (pin "44") (pinfunction "44_44") (pintype "bidirectional"))
      (node (ref "JP7") (pin "3") (pinfunction "3_3") (pintype "passive"))
    )
    (net (code "70") (name "Net-(B1-Pad45)") (class "Default")
      (node (ref "B1") (pin "45") (pinfunction "45_45") (pintype "bidirectional"))
      (node (ref "JP6") (pin "5") (pinfunction "5_5") (pintype "passive"))
    )
    (net (code "71") (name "Net-(B1-Pad46)") (class "Default")
      (node (ref "B1") (pin "46") (pinfunction "46_46") (pintype "bidirectional"))
      (node (ref "JP7") (pin "4") (pinfunction "4_4") (pintype "passive"))
    )
    (net (code "72") (name "Net-(B1-Pad47)") (class "Default")
      (node (ref "B1") (pin "47") (pinfunction "47_47") (pintype "bidirectional"))
      (node (ref "JP6") (pin "4") (pinfunction "4_4") (pintype "passive"))
    )
    (net (code "73") (name "Net-(B1-Pad48)") (class "Default")
      (node (ref "B1") (pin "48") (pinfunction "48_48") (pintype "bidirectional"))
      (node (ref "JP7") (pin "5") (pinfunction "5_5") (pintype "passive"))
    )
    (net (code "74") (name "Net-(B1-Pad49)") (class "Default")
      (node (ref "B1") (pin "49") (pinfunction "49_49") (pintype "bidirectional"))
      (node (ref "JP6") (pin "3") (pinfunction "3_3") (pintype "passive"))
    )
    (net (code "75") (name "Net-(B1-PadA0)") (class "Default")
      (node (ref "B1") (pin "A0") (pinfunction "A0_A0") (pintype "bidirectional"))
      (node (ref "JP3") (pin "9") (pinfunction "9_9") (pintype "passive"))
    )
    (net (code "76") (name "Net-(B1-PadA1)") (class "Default")
      (node (ref "B1") (pin "A1") (pinfunction "A1_A1") (pintype "bidirectional"))
      (node (ref "JP3") (pin "8") (pinfunction "8_8") (pintype "passive"))
    )
    (net (code "77") (name "Net-(B1-PadA2)") (class "Default")
      (node (ref "B1") (pin "A2") (pinfunction "A2_A2") (pintype "bidirectional"))
      (node (ref "JP3") (pin "7") (pinfunction "7_7") (pintype "passive"))
    )
    (net (code "78") (name "Net-(B1-PadA3)") (class "Default")
      (node (ref "B1") (pin "A3") (pinfunction "A3_A3") (pintype "bidirectional"))
      (node (ref "JP3") (pin "6") (pinfunction "6_6") (pintype "passive"))
    )
    (net (code "79") (name "Net-(B1-PadA4)") (class "Default")
      (node (ref "B1") (pin "A4") (pinfunction "A4_A4") (pintype "bidirectional"))
      (node (ref "JP3") (pin "5") (pinfunction "5_5") (pintype "passive"))
    )
    (net (code "80") (name "Net-(B1-PadA5)") (class "Default")
      (node (ref "B1") (pin "A5") (pinfunction "A5_A5") (pintype "bidirectional"))
      (node (ref "JP3") (pin "4") (pinfunction "4_4") (pintype "passive"))
    )
    (net (code "81") (name "Net-(B1-PadA6)") (class "Default")
      (node (ref "B1") (pin "A6") (pinfunction "A6_A6") (pintype "bidirectional"))
      (node (ref "JP3") (pin "3") (pinfunction "3_3") (pintype "passive"))
    )
    (net (code "82") (name "Net-(B1-PadA7)") (class "Default")
      (node (ref "B1") (pin "A7") (pinfunction "A7_A7") (pintype "bidirectional"))
      (node (ref "JP3") (pin "2") (pinfunction "2_2") (pintype "passive"))
    )
    (net (code "83") (name "Net-(B1-PadA8)") (class "Default")
      (node (ref "B1") (pin "A8") (pinfunction "A8_A8") (pintype "bidirectional"))
      (node (ref "JP3") (pin "1") (pinfunction "1_1") (pintype "passive"))
    )
    (net (code "84") (name "Net-(B1-PadA9)") (class "Default")
      (node (ref "B1") (pin "A9") (pinfunction "A9_A9") (pintype "bidirectional"))
      (node (ref "JP14") (pin "2") (pinfunction "2_2") (pintype "passive"))
    )
    (net (code "85") (name "Net-(B1-PadA10)") (class "Default")
      (node (ref "B1") (pin "A10") (pinfunction "A10_A10") (pintype "bidirectional"))
      (node (ref "JP14") (pin "1") (pinfunction "1_1") (pintype "passive"))
    )
    (net (code "86") (name "Net-(B1-PadA11)") (class "Default")
      (node (ref "B1") (pin "A11") (pinfunction "A11_A11") (pintype "bidirectional"))
      (node (ref "JP2") (pin "5") (pinfunction "5_5") (pintype "passive"))
    )
    (net (code "87") (name "Net-(B1-PadA12)") (class "Default")
      (node (ref "B1") (pin "A12") (pinfunction "A12_A12") (pintype "bidirectional"))
      (node (ref "JP2") (pin "4") (pinfunction "4_4") (pintype "passive"))
    )
    (net (code "88") (name "Net-(B1-PadA13)") (class "Default")
      (node (ref "B1") (pin "A13") (pinfunction "A13_A13") (pintype "bidirectional"))
      (node (ref "JP2") (pin "3") (pinfunction "3_3") (pintype "passive"))
    )
    (net (code "89") (name "Net-(B1-PadA14)") (class "Default")
      (node (ref "B1") (pin "A14") (pinfunction "A14_A14") (pintype "bidirectional"))
      (node (ref "JP2") (pin "2") (pinfunction "2_2") (pintype "passive"))
    )
    (net (code "90") (name "Net-(B1-PadA15)") (class "Default")
      (node (ref "B1") (pin "A15") (pinfunction "A15_A15") (pintype "bidirectional"))
      (node (ref "JP2") (pin "1") (pinfunction "1_1") (pintype "passive"))
    )
    (net (code "91") (name "Net-(D1-PadA)") (class "Default")
      (node (ref "D1") (pin "A") (pinfunction "A_A") (pintype "passive"))
      (node (ref "F6") (pin "2") (pinfunction "2_2") (pintype "passive"))
    )
    (net (code "92") (name "Net-(F6-Pad1)") (class "Default")
      (node (ref "F6") (pin "1") (pinfunction "1_1") (pintype "passive"))
      (node (ref "U$3") (pin "P$2") (pinfunction "P$2_P$2") (pintype "bidirectional"))
    )
    (net (code "93") (name "Net-(JP1-Pad1)") (class "Default")
      (node (ref "JP1") (pin "1") (pinfunction "1_1") (pintype "passive"))
      (node (ref "U$1") (pin "D12") (pinfunction "D12_D12") (pintype "bidirectional"))
    )
    (net (code "94") (name "Net-(JP1-Pad2)") (class "Default")
      (node (ref "JP1") (pin "2") (pinfunction "2_2") (pintype "passive"))
      (node (ref "U$1") (pin "D11") (pinfunction "D11_D11") (pintype "bidirectional"))
    )
    (net (code "95") (name "Net-(JP1-Pad3)") (class "Default")
      (node (ref "JP1") (pin "3") (pinfunction "3_3") (pintype "passive"))
      (node (ref "U$1") (pin "D10") (pinfunction "D10_D10") (pintype "bidirectional"))
    )
    (net (code "96") (name "Net-(JP1-Pad4)") (class "Default")
      (node (ref "JP1") (pin "4") (pinfunction "4_4") (pintype "passive"))
      (node (ref "U$1") (pin "D9") (pinfunction "D9_D9") (pintype "bidirectional"))
    )
    (net (code "97") (name "Net-(JP1-Pad5)") (class "Default")
      (node (ref "JP1") (pin "5") (pinfunction "5_5") (pintype "passive"))
      (node (ref "U$1") (pin "D8") (pinfunction "D8_D8") (pintype "bidirectional"))
    )
    (net (code "98") (name "Net-(JP1-Pad6)") (class "Default")
      (node (ref "JP1") (pin "6") (pinfunction "6_6") (pintype "passive"))
      (node (ref "U$1") (pin "D7") (pinfunction "D7_D7") (pintype "bidirectional"))
    )
    (net (code "99") (name "Net-(JP1-Pad7)") (class "Default")
      (node (ref "JP1") (pin "7") (pinfunction "7_7") (pintype "passive"))
      (node (ref "U$1") (pin "D6") (pinfunction "D6_D6") (pintype "bidirectional"))
    )
    (net (code "100") (name "Net-(JP4-Pad1)") (class "Default")
      (node (ref "JP4") (pin "1") (pinfunction "1_1") (pintype "passive"))
      (node (ref "U$1") (pin "A7") (pinfunction "A7_A7") (pintype "bidirectional"))
    )
    (net (code "101") (name "Net-(JP4-Pad2)") (class "Default")
      (node (ref "JP4") (pin "2") (pinfunction "2_2") (pintype "passive"))
      (node (ref "U$1") (pin "A6") (pinfunction "A6_A6") (pintype "bidirectional"))
    )
    (net (code "102") (name "Net-(JP4-Pad3)") (class "Default")
      (node (ref "JP4") (pin "3") (pinfunction "3_3") (pintype "passive"))
      (node (ref "U$1") (pin "A5") (pinfunction "A5_A5") (pintype "bidirectional"))
    )
    (net (code "103") (name "Net-(JP4-Pad4)") (class "Default")
      (node (ref "JP4") (pin "4") (pinfunction "4_4") (pintype "passive"))
      (node (ref "U$1") (pin "A4") (pinfunction "A4_A4") (pintype "bidirectional"))
    )
    (net (code "104") (name "Net-(JP4-Pad5)") (class "Default")
      (node (ref "JP4") (pin "5") (pinfunction "5_5") (pintype "passive"))
      (node (ref "U$1") (pin "A3") (pinfunction "A3_A3") (pintype "bidirectional"))
    )
    (net (code "105") (name "Net-(JP4-Pad6)") (class "Default")
      (node (ref "JP4") (pin "6") (pinfunction "6_6") (pintype "passive"))
      (node (ref "U$1") (pin "A2") (pinfunction "A2_A2") (pintype "bidirectional"))
    )
    (net (code "106") (name "Net-(JP4-Pad7)") (class "Default")
      (node (ref "JP4") (pin "7") (pinfunction "7_7") (pintype "passive"))
      (node (ref "U$1") (pin "A1") (pinfunction "A1_A1") (pintype "bidirectional"))
    )
    (net (code "107") (name "Net-(JP4-Pad8)") (class "Default")
      (node (ref "JP4") (pin "8") (pinfunction "8_8") (pintype "passive"))
      (node (ref "U$1") (pin "A0") (pinfunction "A0_A0") (pintype "bidirectional"))
    )
    (net (code "108") (name "Net-(JP9-Pad1)") (class "Default")
      (node (ref "JP9") (pin "1") (pinfunction "1_1") (pintype "passive"))
      (node (ref "U$1") (pin "RX1") (pinfunction "RX1_RX1") (pintype "bidirectional"))
    )
    (net (code "109") (name "Net-(JP9-Pad2)") (class "Default")
      (node (ref "JP9") (pin "2") (pinfunction "2_2") (pintype "passive"))
      (node (ref "U$1") (pin "TX0") (pinfunction "TX0_TX0") (pintype "bidirectional"))
    )
    (net (code "110") (name "Net-(JP15-Pad1)") (class "Default")
      (node (ref "JP15") (pin "1") (pinfunction "1_1") (pintype "passive"))
      (node (ref "R6") (pin "1") (pinfunction "1_1") (pintype "passive"))
    )
    (net (code "111") (name "Net-(JP16-Pad1)") (class "Default")
      (node (ref "JP16") (pin "1") (pinfunction "1_1") (pintype "passive"))
      (node (ref "R7") (pin "1") (pinfunction "1_1") (pintype "passive"))
    )
    (net (code "112") (name "Net-(JP17-Pad1)") (class "Default")
      (node (ref "JP17") (pin "1") (pinfunction "1_1") (pintype "passive"))
      (node (ref "U$1") (pin "D13") (pinfunction "D13_D13") (pintype "bidirectional"))
    )
    (net (code "113") (name "Net-(LED12V-C)") (class "Default")
      (node (ref "LED12V") (pin "K") (pinfunction "C_K") (pintype "passive"))
      (node (ref "R4") (pin "2") (pinfunction "2_2") (pintype "passive"))
    )
    (net (code "114") (name "Net-(LED12V1-C)") (class "Default")
      (node (ref "LED12V1") (pin "K") (pinfunction "C_K") (pintype "passive"))
      (node (ref "R8") (pin "2") (pinfunction "2_2") (pintype "passive"))
    )
    (net (code "115") (name "Net-(LED12V2-C)") (class "Default")
      (node (ref "LED12V2") (pin "K") (pinfunction "C_K") (pintype "passive"))
      (node (ref "R9") (pin "2") (pinfunction "2_2") (pintype "passive"))
    )
    (net (code "116") (name "Net-(LED12V3-C)") (class "Default")
      (node (ref "LED12V3") (pin "K") (pinfunction "C_K") (pintype "passive"))
      (node (ref "R10") (pin "2") (pinfunction "2_2") (pintype "passive"))
    )
    (net (code "117") (name "Net-(LED12V4-C)") (class "Default")
      (node (ref "LED12V4") (pin "K") (pinfunction "C_K") (pintype "passive"))
      (node (ref "R11") (pin "2") (pinfunction "2_2") (pintype "passive"))
    )
    (net (code "118") (name "Net-(LED12V5-C)") (class "Default")
      (node (ref "LED12V5") (pin "K") (pinfunction "C_K") (pintype "passive"))
      (node (ref "R12") (pin "2") (pinfunction "2_2") (pintype "passive"))
    )
    (net (code "119") (name "Net-(LED12V6-C)") (class "Default")
      (node (ref "LED12V6") (pin "K") (pinfunction "C_K") (pintype "passive"))
      (node (ref "R13") (pin "2") (pinfunction "2_2") (pintype "passive"))
    )
    (net (code "120") (name "Net-(LED12V7-C)") (class "Default")
      (node (ref "LED12V7") (pin "K") (pinfunction "C_K") (pintype "passive"))
      (node (ref "R14") (pin "2") (pinfunction "2_2") (pintype "passive"))
    )
    (net (code "121") (name "Net-(LED12V8-C)") (class "Default")
      (node (ref "LED12V8") (pin "K") (pinfunction "C_K") (pintype "passive"))
      (node (ref "R15") (pin "2") (pinfunction "2_2") (pintype "passive"))
    )
    (net (code "122") (name "Net-(LED12V9-C)") (class "Default")
      (node (ref "LED12V9") (pin "K") (pinfunction "C_K") (pintype "passive"))
      (node (ref "R16") (pin "2") (pinfunction "2_2") (pintype "passive"))
    )
    (net (code "123") (name "Net-(LED12V10-C)") (class "Default")
      (node (ref "LED12V10") (pin "K") (pinfunction "C_K") (pintype "passive"))
      (node (ref "R17") (pin "2") (pinfunction "2_2") (pintype "passive"))
    )
    (net (code "124") (name "Net-(LED12V11-C)") (class "Default")
      (node (ref "LED12V11") (pin "K") (pinfunction "C_K") (pintype "passive"))
      (node (ref "R18") (pin "2") (pinfunction "2_2") (pintype "passive"))
    )
    (net (code "125") (name "Net-(LED12V12-C)") (class "Default")
      (node (ref "LED12V12") (pin "K") (pinfunction "C_K") (pintype "passive"))
      (node (ref "R19") (pin "2") (pinfunction "2_2") (pintype "passive"))
    )
    (net (code "126") (name "Net-(LED12V13-C)") (class "Default")
      (node (ref "LED12V13") (pin "K") (pinfunction "C_K") (pintype "passive"))
      (node (ref "R20") (pin "2") (pinfunction "2_2") (pintype "passive"))
    )
    (net (code "127") (name "Net-(LED12V14-C)") (class "Default")
      (node (ref "LED12V14") (pin "K") (pinfunction "C_K") (pintype "passive"))
      (node (ref "R21") (pin "2") (pinfunction "2_2") (pintype "passive"))
    )
    (net (code "128") (name "Net-(LED12V15-C)") (class "Default")
      (node (ref "LED12V15") (pin "K") (pinfunction "C_K") (pintype "passive"))
      (node (ref "R22") (pin "2") (pinfunction "2_2") (pintype "passive"))
    )
    (net (code "129") (name "Net-(LED12V16-C)") (class "Default")
      (node (ref "LED12V16") (pin "K") (pinfunction "C_K") (pintype "passive"))
      (node (ref "R23") (pin "2") (pinfunction "2_2") (pintype "passive"))
    )
    (net (code "130") (name "Net-(LED12V17-C)") (class "Default")
      (node (ref "LED12V17") (pin "K") (pinfunction "C_K") (pintype "passive"))
      (node (ref "R24") (pin "2") (pinfunction "2_2") (pintype "passive"))
    )
    (net (code "131") (name "Net-(LED12V18-C)") (class "Default")
      (node (ref "LED12V18") (pin "K") (pinfunction "C_K") (pintype "passive"))
      (node (ref "R25") (pin "2") (pinfunction "2_2") (pintype "passive"))
    )
    (net (code "132") (name "Net-(LED12V19-C)") (class "Default")
      (node (ref "LED12V19") (pin "K") (pinfunction "C_K") (pintype "passive"))
      (node (ref "R26") (pin "2") (pinfunction "2_2") (pintype "passive"))
    )
    (net (code "133") (name "Net-(LED12V20-C)") (class "Default")
      (node (ref "LED12V20") (pin "K") (pinfunction "C_K") (pintype "passive"))
      (node (ref "R27") (pin "2") (pinfunction "2_2") (pintype "passive"))
    )
    (net (code "134") (name "Net-(LED12V21-C)") (class "Default")
      (node (ref "LED12V21") (pin "K") (pinfunction "C_K") (pintype "passive"))
      (node (ref "R28") (pin "2") (pinfunction "2_2") (pintype "passive"))
    )
    (net (code "135") (name "Net-(LED24V-C)") (class "Default")
      (node (ref "LED24V") (pin "K") (pinfunction "C_K") (pintype "passive"))
      (node (ref "R1") (pin "2") (pinfunction "2_2") (pintype "passive"))
    )
    (net (code "136") (name "Net-(T1-B)") (class "Default")
      (node (ref "R6") (pin "2") (pinfunction "2_2") (pintype "passive"))
      (node (ref "T1") (pin "1") (pinfunction "B_1") (pintype "passive"))
    )
    (net (code "137") (name "Net-(T2-B)") (class "Default")
      (node (ref "R7") (pin "2") (pinfunction "2_2") (pintype "passive"))
      (node (ref "T2") (pin "1") (pinfunction "B_1") (pintype "passive"))
    )
    (net (code "138") (name "Net-(ULN.1-I1)") (class "Default")
      (node (ref "JP10") (pin "7") (pinfunction "7_7") (pintype "passive"))
      (node (ref "ULN.1") (pin "1") (pinfunction "I1_1") (pintype "input"))
    )
    (net (code "139") (name "Net-(ULN.1-I2)") (class "Default")
      (node (ref "JP10") (pin "6") (pinfunction "6_6") (pintype "passive"))
      (node (ref "ULN.1") (pin "2") (pinfunction "I2_2") (pintype "input"))
    )
    (net (code "140") (name "Net-(ULN.1-I3)") (class "Default")
      (node (ref "JP10") (pin "5") (pinfunction "5_5") (pintype "passive"))
      (node (ref "ULN.1") (pin "3") (pinfunction "I3_3") (pintype "input"))
    )
    (net (code "141") (name "Net-(ULN.1-I4)") (class "Default")
      (node (ref "JP10") (pin "4") (pinfunction "4_4") (pintype "passive"))
      (node (ref "ULN.1") (pin "4") (pinfunction "I4_4") (pintype "input"))
    )
    (net (code "142") (name "Net-(ULN.1-I5)") (class "Default")
      (node (ref "JP10") (pin "3") (pinfunction "3_3") (pintype "passive"))
      (node (ref "ULN.1") (pin "5") (pinfunction "I5_5") (pintype "input"))
    )
    (net (code "143") (name "Net-(ULN.1-I6)") (class "Default")
      (node (ref "JP10") (pin "2") (pinfunction "2_2") (pintype "passive"))
      (node (ref "ULN.1") (pin "6") (pinfunction "I6_6") (pintype "input"))
    )
    (net (code "144") (name "Net-(ULN.1-I7)") (class "Default")
      (node (ref "JP10") (pin "1") (pinfunction "1_1") (pintype "passive"))
      (node (ref "ULN.1") (pin "7") (pinfunction "I7_7") (pintype "input"))
    )
    (net (code "145") (name "Net-(ULN.2-I1)") (class "Default")
      (node (ref "JP8") (pin "7") (pinfunction "7_7") (pintype "passive"))
      (node (ref "ULN.2") (pin "1") (pinfunction "I1_1") (pintype "input"))
    )
    (net (code "146") (name "Net-(ULN.2-I2)") (class "Default")
      (node (ref "JP8") (pin "6") (pinfunction "6_6") (pintype "passive"))
      (node (ref "ULN.2") (pin "2") (pinfunction "I2_2") (pintype "input"))
    )
    (net (code "147") (name "Net-(ULN.2-I3)") (class "Default")
      (node (ref "JP8") (pin "5") (pinfunction "5_5") (pintype "passive"))
      (node (ref "ULN.2") (pin "3") (pinfunction "I3_3") (pintype "input"))
    )
    (net (code "148") (name "Net-(ULN.2-I4)") (class "Default")
      (node (ref "JP8") (pin "4") (pinfunction "4_4") (pintype "passive"))
      (node (ref "ULN.2") (pin "4") (pinfunction "I4_4") (pintype "input"))
    )
    (net (code "149") (name "Net-(ULN.2-I5)") (class "Default")
      (node (ref "JP8") (pin "3") (pinfunction "3_3") (pintype "passive"))
      (node (ref "ULN.2") (pin "5") (pinfunction "I5_5") (pintype "input"))
    )
    (net (code "150") (name "Net-(ULN.2-I6)") (class "Default")
      (node (ref "JP8") (pin "2") (pinfunction "2_2") (pintype "passive"))
      (node (ref "ULN.2") (pin "6") (pinfunction "I6_6") (pintype "input"))
    )
    (net (code "151") (name "Net-(ULN.2-I7)") (class "Default")
      (node (ref "JP8") (pin "1") (pinfunction "1_1") (pintype "passive"))
      (node (ref "ULN.2") (pin "7") (pinfunction "I7_7") (pintype "input"))
    )
    (net (code "152") (name "PWM.A") (class "Default")
      (node (ref "B1") (pin "13") (pinfunction "13_13") (pintype "bidirectional"))
      (node (ref "DRIVER.1") (pin "2") (pinfunction "2_2") (pintype "passive"))
    )
    (net (code "153") (name "PWM.B") (class "Default")
      (node (ref "B1") (pin "12") (pinfunction "12_12") (pintype "bidirectional"))
      (node (ref "DRIVER.1") (pin "4") (pinfunction "4_4") (pintype "passive"))
    )
    (net (code "154") (name "PWM.C") (class "Default")
      (node (ref "B1") (pin "11") (pinfunction "11_11") (pintype "bidirectional"))
      (node (ref "DRIVER.2") (pin "2") (pinfunction "2_2") (pintype "passive"))
    )
    (net (code "155") (name "PWM.D") (class "Default")
      (node (ref "B1") (pin "10") (pinfunction "10_10") (pintype "bidirectional"))
      (node (ref "DRIVER.2") (pin "4") (pinfunction "4_4") (pintype "passive"))
    )
    (net (code "156") (name "RESET.MEGA") (class "Default")
      (node (ref "B1") (pin "RESET") (pinfunction "~{RESET}_RESET") (pintype "bidirectional"))
      (node (ref "R5") (pin "1") (pinfunction "1_1") (pintype "passive"))
      (node (ref "U$2") (pin "2") (pinfunction "2_2") (pintype "bidirectional"))
    )
    (net (code "157") (name "RX.BLUE") (class "Default")
      (node (ref "BLUETOOTH") (pin "2") (pinfunction "2_2") (pintype "passive"))
      (node (ref "R2") (pin "1") (pinfunction "1_1") (pintype "passive"))
      (node (ref "R3") (pin "2") (pinfunction "2_2") (pintype "passive"))
    )
    (net (code "158") (name "RX.NANO") (class "Default")
      (node (ref "B1") (pin "14") (pinfunction "14(TX3)_14") (pintype "bidirectional"))
      (node (ref "U$1") (pin "D5") (pinfunction "D5_D5") (pintype "bidirectional"))
    )
    (net (code "159") (name "STATE") (class "Default")
      (node (ref "BLUETOOTH") (pin "1") (pinfunction "1_1") (pintype "passive"))
      (node (ref "LED12V18") (pin "A") (pinfunction "A_A") (pintype "passive"))
    )
    (net (code "160") (name "TX.BLUE") (class "Default")
      (node (ref "B1") (pin "17") (pinfunction "17(RX2)_17") (pintype "bidirectional"))
      (node (ref "BLUETOOTH") (pin "3") (pinfunction "3_3") (pintype "passive"))
    )
    (net (code "161") (name "TX.MEGA") (class "Default")
      (node (ref "B1") (pin "16") (pinfunction "16(TX2)_16") (pintype "bidirectional"))
      (node (ref "R2") (pin "2") (pinfunction "2_2") (pintype "passive"))
    )
    (net (code "162") (name "TX.NANO") (class "Default")
      (node (ref "B1") (pin "15") (pinfunction "15(RX3)_15") (pintype "bidirectional"))
      (node (ref "U$1") (pin "D4") (pinfunction "D4_D4") (pintype "bidirectional"))
    )
    (net (code "163") (name "unconnected-(B1-Pad3.3V)") (class "Default")
      (node (ref "B1") (pin "3.3V") (pinfunction "3.3V_3.3V") (pintype "bidirectional"))
    )
    (net (code "164") (name "unconnected-(B1-PadAREF)") (class "Default")
      (node (ref "B1") (pin "AREF") (pinfunction "AREF_AREF") (pintype "bidirectional"))
    )
    (net (code "165") (name "unconnected-(B1-PadIOREF)") (class "Default")
      (node (ref "B1") (pin "IOREF") (pinfunction "IOREF_IOREF") (pintype "bidirectional"))
    )
    (net (code "166") (name "unconnected-(B1-PadSCL)") (class "Default")
      (node (ref "B1") (pin "SCL") (pinfunction "SCL_SCL") (pintype "bidirectional"))
    )
    (net (code "167") (name "unconnected-(B1-PadSDA)") (class "Default")
      (node (ref "B1") (pin "SDA") (pinfunction "SDA_SDA") (pintype "bidirectional"))
    )
    (net (code "168") (name "unconnected-(U$1-PadAREF)") (class "Default")
      (node (ref "U$1") (pin "AREF") (pinfunction "AREF_AREF") (pintype "bidirectional"))
    )
    (net (code "169") (name "unconnected-(U$1-PadRST)") (class "Default")
      (node (ref "U$1") (pin "RST") (pinfunction "RST_RST") (pintype "bidirectional"))
    )
    (net (code "170") (name "unconnected-(U$1-PadRST1)") (class "Default")
      (node (ref "U$1") (pin "RST1") (pinfunction "RST1_RST1") (pintype "bidirectional"))
    )
  )
)
